# robot_controller.net
KiCad netlist of a schematic drawn in EAGLE
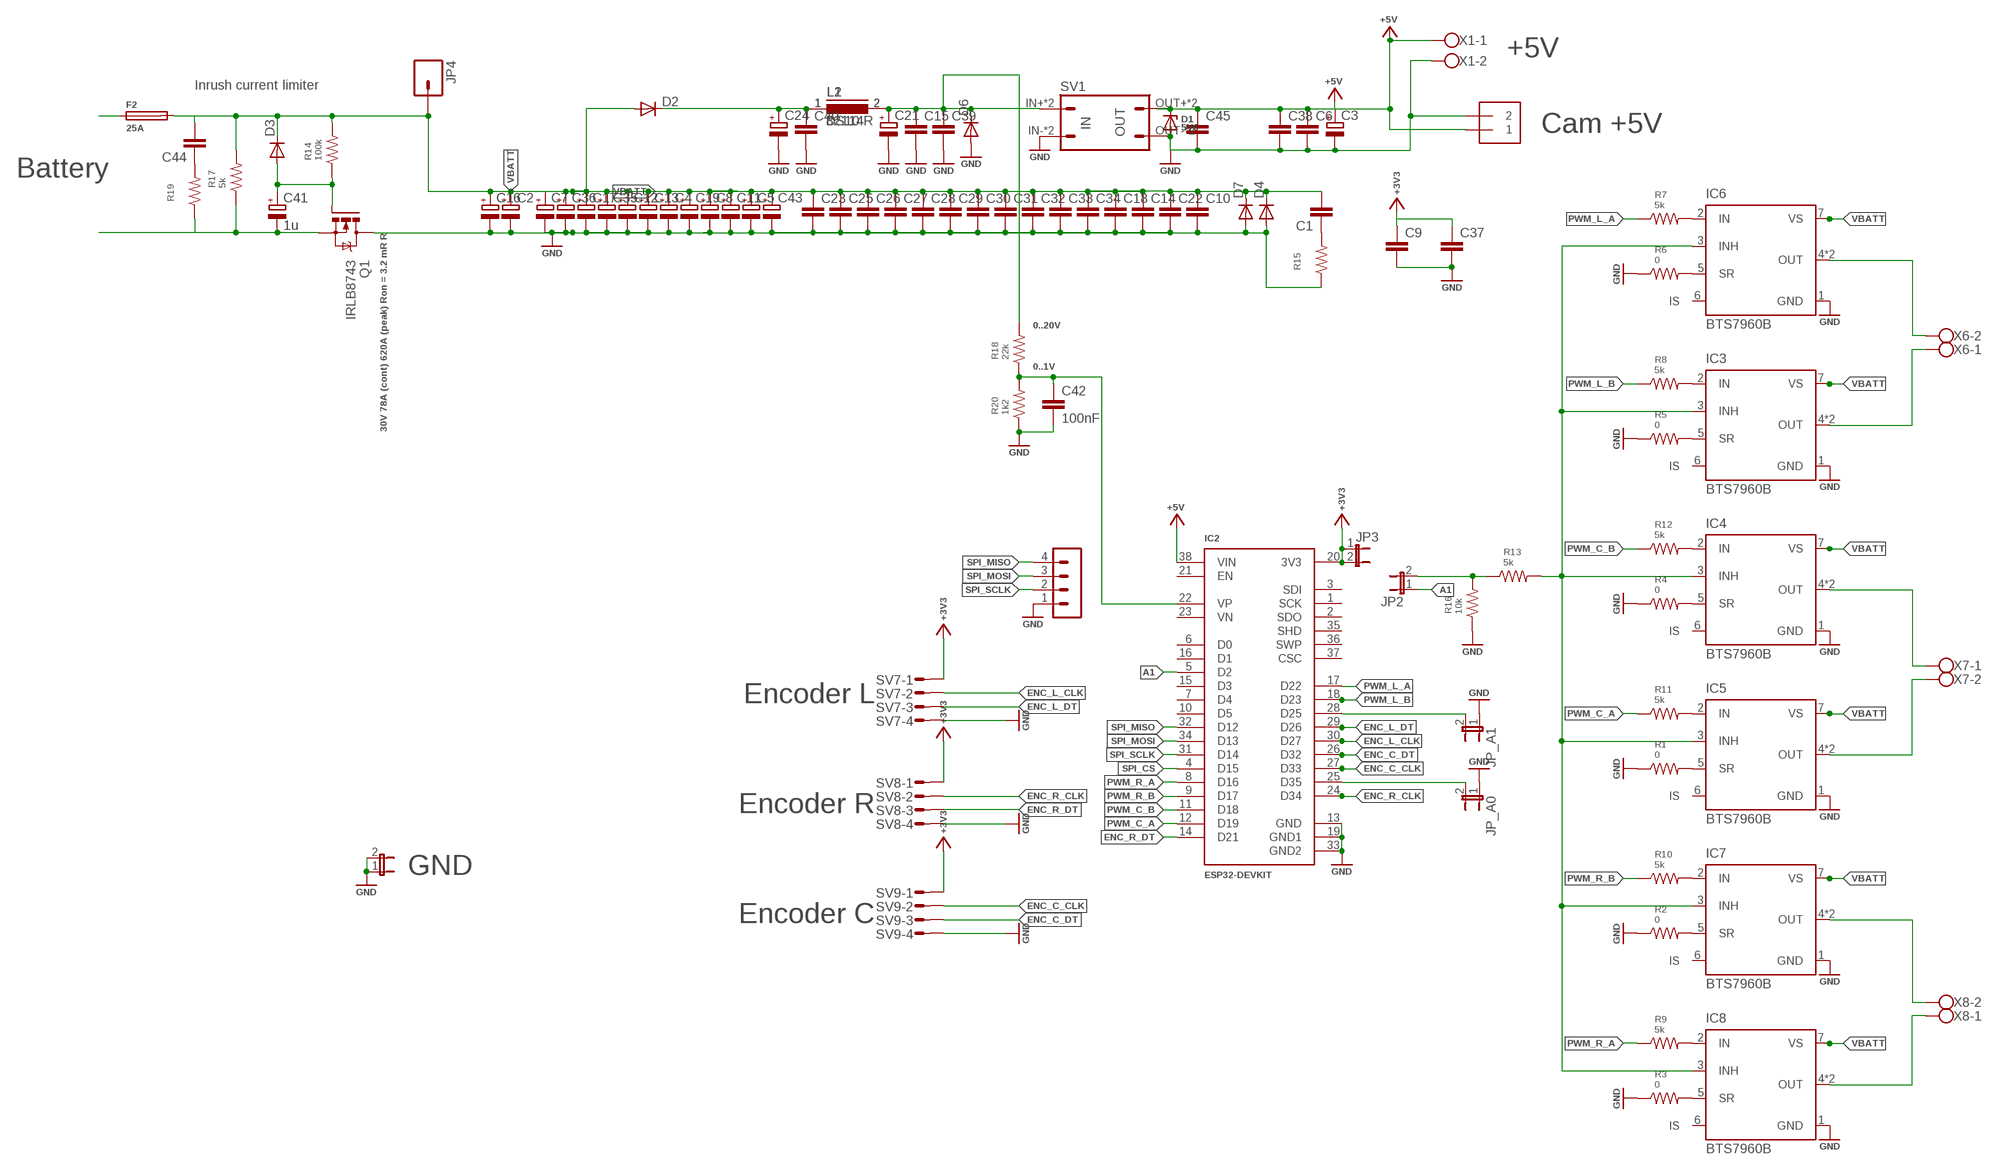
[diagram p0: schematic, sheet 1]

(export (version "E")
  (design (tool "Eeschema 10.0.6"))
  (components
    (comp (ref "C1")
      (value "C-EU025-025X050")
      (footprint "eagle-import:C025-025X050")
      (libsource (lib "eagle-import") (part "C-EU025-025X050"))
    )
    (comp (ref "C2")
      (value "CPOL-EUE5-10.5")
      (footprint "eagle-import:E5-10,5")
      (libsource (lib "eagle-import") (part "CPOL-EUE5-10.5"))
    )
    (comp (ref "C3")
      (value "CPOL-EUE5-10.5")
      (footprint "eagle-import:E5-10,5")
      (libsource (lib "eagle-import") (part "CPOL-EUE5-10.5"))
    )
    (comp (ref "C4")
      (value "CPOL-EUE5-10.5")
      (footprint "eagle-import:E5-10,5")
      (libsource (lib "eagle-import") (part "CPOL-EUE5-10.5"))
    )
    (comp (ref "C5")
      (value "CPOL-EUE5-10.5")
      (footprint "eagle-import:E5-10,5")
      (libsource (lib "eagle-import") (part "CPOL-EUE5-10.5"))
    )
    (comp (ref "C6")
      (value "C-EUC1206")
      (footprint "eagle-import:C1206")
      (libsource (lib "eagle-import") (part "C-EUC1206"))
    )
    (comp (ref "C7")
      (value "CPOL-EUE5-10.5")
      (footprint "eagle-import:E5-10,5")
      (libsource (lib "eagle-import") (part "CPOL-EUE5-10.5"))
    )
    (comp (ref "C8")
      (value "CPOL-EUE5-10.5")
      (footprint "eagle-import:E5-10,5")
      (libsource (lib "eagle-import") (part "CPOL-EUE5-10.5"))
    )
    (comp (ref "C9")
      (value "C-EUC1206")
      (footprint "eagle-import:C1206")
      (libsource (lib "eagle-import") (part "C-EUC1206"))
    )
    (comp (ref "C10")
      (value "C-EUC1206")
      (footprint "eagle-import:C1206")
      (libsource (lib "eagle-import") (part "C-EUC1206"))
    )
    (comp (ref "C11")
      (value "CPOL-EUE5-10.5")
      (footprint "eagle-import:E5-10,5")
      (libsource (lib "eagle-import") (part "CPOL-EUE5-10.5"))
    )
    (comp (ref "C12")
      (value "CPOL-EUE5-10.5")
      (footprint "eagle-import:E5-10,5")
      (libsource (lib "eagle-import") (part "CPOL-EUE5-10.5"))
    )
    (comp (ref "C13")
      (value "CPOL-EUE5-10.5")
      (footprint "eagle-import:E5-10,5")
      (libsource (lib "eagle-import") (part "CPOL-EUE5-10.5"))
    )
    (comp (ref "C14")
      (value "C-EUC1206")
      (footprint "eagle-import:C1206")
      (libsource (lib "eagle-import") (part "C-EUC1206"))
    )
    (comp (ref "C15")
      (value "C-EUC1206")
      (footprint "eagle-import:C1206")
      (libsource (lib "eagle-import") (part "C-EUC1206"))
    )
    (comp (ref "C16")
      (value "CPOL-EUE5-10.5")
      (footprint "eagle-import:E5-10,5")
      (libsource (lib "eagle-import") (part "CPOL-EUE5-10.5"))
    )
    (comp (ref "C17")
      (value "CPOL-EUE5-10.5")
      (footprint "eagle-import:E5-10,5")
      (libsource (lib "eagle-import") (part "CPOL-EUE5-10.5"))
    )
    (comp (ref "C18")
      (value "C-EUC1206")
      (footprint "eagle-import:C1206")
      (libsource (lib "eagle-import") (part "C-EUC1206"))
    )
    (comp (ref "C19")
      (value "CPOL-EUE5-10.5")
      (footprint "eagle-import:E5-10,5")
      (libsource (lib "eagle-import") (part "CPOL-EUE5-10.5"))
    )
    (comp (ref "C21")
      (value "CPOL-EUE5-10.5")
      (footprint "eagle-import:E5-10,5")
      (libsource (lib "eagle-import") (part "CPOL-EUE5-10.5"))
    )
    (comp (ref "C22")
      (value "C-EUC1206")
      (footprint "eagle-import:C1206")
      (libsource (lib "eagle-import") (part "C-EUC1206"))
    )
    (comp (ref "C23")
      (value "C-EUC1206")
      (footprint "eagle-import:C1206")
      (libsource (lib "eagle-import") (part "C-EUC1206"))
    )
    (comp (ref "C24")
      (value "CPOL-EUE5-10.5")
      (footprint "eagle-import:E5-10,5")
      (libsource (lib "eagle-import") (part "CPOL-EUE5-10.5"))
    )
    (comp (ref "C25")
      (value "C-EUC1206")
      (footprint "eagle-import:C1206")
      (libsource (lib "eagle-import") (part "C-EUC1206"))
    )
    (comp (ref "C26")
      (value "C-EUC1206")
      (footprint "eagle-import:C1206")
      (libsource (lib "eagle-import") (part "C-EUC1206"))
    )
    (comp (ref "C27")
      (value "C-EUC1206")
      (footprint "eagle-import:C1206")
      (libsource (lib "eagle-import") (part "C-EUC1206"))
    )
    (comp (ref "C28")
      (value "C-EUC1206")
      (footprint "eagle-import:C1206")
      (libsource (lib "eagle-import") (part "C-EUC1206"))
    )
    (comp (ref "C29")
      (value "C-EUC1206")
      (footprint "eagle-import:C1206")
      (libsource (lib "eagle-import") (part "C-EUC1206"))
    )
    (comp (ref "C30")
      (value "C-EUC1206")
      (footprint "eagle-import:C1206")
      (libsource (lib "eagle-import") (part "C-EUC1206"))
    )
    (comp (ref "C31")
      (value "C-EUC1206")
      (footprint "eagle-import:C1206")
      (libsource (lib "eagle-import") (part "C-EUC1206"))
    )
    (comp (ref "C32")
      (value "C-EUC1206")
      (footprint "eagle-import:C1206")
      (libsource (lib "eagle-import") (part "C-EUC1206"))
    )
    (comp (ref "C33")
      (value "C-EUC1206")
      (footprint "eagle-import:C1206")
      (libsource (lib "eagle-import") (part "C-EUC1206"))
    )
    (comp (ref "C34")
      (value "C-EUC1206")
      (footprint "eagle-import:C1206")
      (libsource (lib "eagle-import") (part "C-EUC1206"))
    )
    (comp (ref "C35")
      (value "CPOL-EUE5-10.5")
      (footprint "eagle-import:E5-10,5")
      (libsource (lib "eagle-import") (part "CPOL-EUE5-10.5"))
    )
    (comp (ref "C36")
      (value "CPOL-EUE5-10.5")
      (footprint "eagle-import:E5-10,5")
      (libsource (lib "eagle-import") (part "CPOL-EUE5-10.5"))
    )
    (comp (ref "C37")
      (value "C-EUC1206")
      (footprint "eagle-import:C1206")
      (libsource (lib "eagle-import") (part "C-EUC1206"))
    )
    (comp (ref "C38")
      (value "C-EUC1206")
      (footprint "eagle-import:C1206")
      (libsource (lib "eagle-import") (part "C-EUC1206"))
    )
    (comp (ref "C39")
      (value "C-EUC1206")
      (footprint "eagle-import:C1206")
      (libsource (lib "eagle-import") (part "C-EUC1206"))
    )
    (comp (ref "C40")
      (value "C-EUC1206")
      (footprint "eagle-import:C1206")
      (libsource (lib "eagle-import") (part "C-EUC1206"))
    )
    (comp (ref "C41")
      (value "1u")
      (footprint "eagle-import:E2,5-6")
      (libsource (lib "eagle-import") (part "CPOL-EUE2.5-6"))
    )
    (comp (ref "C42")
      (value "100nF")
      (footprint "eagle-import:C1206")
      (libsource (lib "eagle-import") (part "C-EUC1206"))
    )
    (comp (ref "C43")
      (value "CPOL-EUE5-10.5")
      (footprint "eagle-import:E5-10,5")
      (libsource (lib "eagle-import") (part "CPOL-EUE5-10.5"))
    )
    (comp (ref "C44")
      (value "C-EU050-030X075")
      (footprint "eagle-import:C050-030X075")
      (libsource (lib "eagle-import") (part "C-EU050-030X075"))
    )
    (comp (ref "C45")
      (value "C-EUC1206")
      (footprint "eagle-import:C1206")
      (libsource (lib "eagle-import") (part "C-EUC1206"))
    )
    (comp (ref "D1")
      (value "5V6")
      (footprint "eagle-import:DO41Z10")
      (libsource (lib "eagle-import") (part "ZENER-DIODEDO41Z10"))
    )
    (comp (ref "D2")
      (value "DIODE-DO15-12")
      (footprint "eagle-import:DO15-12")
      (libsource (lib "eagle-import") (part "DIODE-DO15-12"))
    )
    (comp (ref "D3")
      (value "DIODE-DO-214AC")
      (footprint "eagle-import:DO-214AC")
      (libsource (lib "eagle-import") (part "diode_smd_DIODE-DO-214AC"))
    )
    (comp (ref "D4")
      (value "DIODE-DO41-7.6")
      (footprint "eagle-import:DO41-7.6")
      (libsource (lib "eagle-import") (part "diode_smd_DIODE-DO41-7.6"))
    )
    (comp (ref "D6")
      (value "DIODE-DO15-12")
      (footprint "eagle-import:DO15-12")
      (libsource (lib "eagle-import") (part "DIODE-DO15-12"))
    )
    (comp (ref "D7")
      (value "DIODE-DO41-7.6")
      (footprint "eagle-import:DO41-7.6")
      (libsource (lib "eagle-import") (part "diode_smd_DIODE-DO41-7.6"))
    )
    (comp (ref "F2")
      (value "25A")
      (footprint "eagle-import:SHK20L")
      (libsource (lib "eagle-import") (part "19559"))
    )
    (comp (ref "IC2")
      (value "ESP32-DEVKIT")
      (footprint "eagle-import:DEVKIT-V1-NOHOLES")
      (libsource (lib "eagle-import") (part "ESP32-DEVKIT-V1NOHOLES"))
    )
    (comp (ref "IC3")
      (value "BTS7960B")
      (footprint "eagle-import:P-TO263-7-1")
      (libsource (lib "eagle-import") (part "TLE5205-2G"))
    )
    (comp (ref "IC4")
      (value "BTS7960B")
      (footprint "eagle-import:P-TO263-7-1")
      (libsource (lib "eagle-import") (part "TLE5205-2G"))
    )
    (comp (ref "IC5")
      (value "BTS7960B")
      (footprint "eagle-import:P-TO263-7-1")
      (libsource (lib "eagle-import") (part "TLE5205-2G"))
    )
    (comp (ref "IC6")
      (value "BTS7960B")
      (footprint "eagle-import:P-TO263-7-1")
      (libsource (lib "eagle-import") (part "TLE5205-2G"))
    )
    (comp (ref "IC7")
      (value "BTS7960B")
      (footprint "eagle-import:P-TO263-7-1")
      (libsource (lib "eagle-import") (part "TLE5205-2G"))
    )
    (comp (ref "IC8")
      (value "BTS7960B")
      (footprint "eagle-import:P-TO263-7-1")
      (libsource (lib "eagle-import") (part "TLE5205-2G"))
    )
    (comp (ref "J6")
      (value "1X2-3.5MM")
      (footprint "eagle-import:3.5MMTERM")
      (libsource (lib "eagle-import") (part "1X2-3.5MM"))
    )
    (comp (ref "JP1")
      (value "JP1E")
      (footprint "eagle-import:JP1")
      (libsource (lib "eagle-import") (part "JP1E"))
    )
    (comp (ref "JP2")
      (value "JP1E")
      (footprint "eagle-import:JP1")
      (libsource (lib "eagle-import") (part "JP1E"))
    )
    (comp (ref "JP3")
      (value "JP1E")
      (footprint "eagle-import:JP1")
      (libsource (lib "eagle-import") (part "JP1E"))
    )
    (comp (ref "JP4")
      (value "M01PTH_LONGPAD")
      (footprint "eagle-import:1X01_LONGPAD")
      (libsource (lib "eagle-import") (part "M01PTH_LONGPAD"))
    )
    (comp (ref "JP_A0")
      (value "JP1E")
      (footprint "eagle-import:JP1")
      (libsource (lib "eagle-import") (part "JP1E"))
    )
    (comp (ref "JP_A1")
      (value "JP1E")
      (footprint "eagle-import:JP1")
      (libsource (lib "eagle-import") (part "JP1E"))
    )
    (comp (ref "L1")
      (value "82114R")
      (footprint "eagle-import:82114R")
      (libsource (lib "eagle-import") (part "82114R"))
    )
    (comp (ref "L2")
      (value "DS10")
      (footprint "eagle-import:DS10")
      (libsource (lib "eagle-import") (part "DS10"))
    )
    (comp (ref "Q1")
      (value "IRLB8743")
      (footprint "eagle-import:TO220BV")
      (libsource (lib "eagle-import") (part "IRF540"))
    )
    (comp (ref "R1")
      (value "0")
      (footprint "eagle-import:R1206")
      (libsource (lib "eagle-import") (part "R-US_R1206"))
    )
    (comp (ref "R2")
      (value "0")
      (footprint "eagle-import:R1206")
      (libsource (lib "eagle-import") (part "R-US_R1206"))
    )
    (comp (ref "R3")
      (value "0")
      (footprint "eagle-import:R1206")
      (libsource (lib "eagle-import") (part "R-US_R1206"))
    )
    (comp (ref "R4")
      (value "0")
      (footprint "eagle-import:R1206")
      (libsource (lib "eagle-import") (part "R-US_R1206"))
    )
    (comp (ref "R5")
      (value "0")
      (footprint "eagle-import:R1206")
      (libsource (lib "eagle-import") (part "R-US_R1206"))
    )
    (comp (ref "R6")
      (value "0")
      (footprint "eagle-import:R1206")
      (libsource (lib "eagle-import") (part "R-US_R1206"))
    )
    (comp (ref "R7")
      (value "5k")
      (footprint "eagle-import:R1206")
      (libsource (lib "eagle-import") (part "R-US_R1206"))
    )
    (comp (ref "R8")
      (value "5k")
      (footprint "eagle-import:R1206")
      (libsource (lib "eagle-import") (part "R-US_R1206"))
    )
    (comp (ref "R9")
      (value "5k")
      (footprint "eagle-import:R1206")
      (libsource (lib "eagle-import") (part "R-US_R1206"))
    )
    (comp (ref "R10")
      (value "5k")
      (footprint "eagle-import:R1206")
      (libsource (lib "eagle-import") (part "R-US_R1206"))
    )
    (comp (ref "R11")
      (value "5k")
      (footprint "eagle-import:R1206")
      (libsource (lib "eagle-import") (part "R-US_R1206"))
    )
    (comp (ref "R12")
      (value "5k")
      (footprint "eagle-import:R1206")
      (libsource (lib "eagle-import") (part "R-US_R1206"))
    )
    (comp (ref "R13")
      (value "5k")
      (footprint "eagle-import:R1206")
      (libsource (lib "eagle-import") (part "R-US_R1206"))
    )
    (comp (ref "R14")
      (value "100k")
      (footprint "eagle-import:R1206")
      (libsource (lib "eagle-import") (part "R-US_R1206"))
    )
    (comp (ref "R15")
      (value "R-US_0411/3V")
      (footprint "eagle-import:0411V")
      (libsource (lib "eagle-import") (part "R-US_0411/3V"))
    )
    (comp (ref "R16")
      (value "10k")
      (footprint "eagle-import:R1206")
      (libsource (lib "eagle-import") (part "R-US_R1206"))
    )
    (comp (ref "R17")
      (value "5k")
      (footprint "eagle-import:R1206")
      (libsource (lib "eagle-import") (part "R-US_R1206"))
    )
    (comp (ref "R18")
      (value "22k")
      (footprint "eagle-import:R1206")
      (libsource (lib "eagle-import") (part "R-US_R1206"))
    )
    (comp (ref "R19")
      (value "R-US_0617/5V")
      (footprint "eagle-import:0617V")
      (libsource (lib "eagle-import") (part "R-US_0617/5V"))
    )
    (comp (ref "R20")
      (value "1k2")
      (footprint "eagle-import:R1206")
      (libsource (lib "eagle-import") (part "R-US_R1206"))
    )
    (comp (ref "SV1")
      (value "MA04-1SMALL")
      (footprint "eagle-import:MA04-2")
      (libsource (lib "eagle-import") (part "MA04-1SMALL"))
    )
    (comp (ref "SV6")
      (value "MA04-1")
      (footprint "eagle-import:MA04-1")
      (libsource (lib "eagle-import") (part "MA04-1"))
    )
    (comp (ref "SV7")
      (value "MT6-4")
      (footprint "eagle-import:MT6-4")
      (libsource (lib "eagle-import") (part "MT6-4"))
    )
    (comp (ref "SV8")
      (value "MT6-4")
      (footprint "eagle-import:MT6-4")
      (libsource (lib "eagle-import") (part "MT6-4"))
    )
    (comp (ref "SV9")
      (value "MT6-4")
      (footprint "eagle-import:MT6-4")
      (libsource (lib "eagle-import") (part "MT6-4"))
    )
    (comp (ref "X1")
      (value "W239-302")
      (footprint "eagle-import:W239-302")
      (libsource (lib "eagle-import") (part "W239-302"))
    )
    (comp (ref "X6")
      (value "W239-302")
      (footprint "eagle-import:W239-302")
      (libsource (lib "eagle-import") (part "W239-302"))
    )
    (comp (ref "X7")
      (value "W239-302")
      (footprint "eagle-import:W239-302")
      (libsource (lib "eagle-import") (part "W239-302"))
    )
    (comp (ref "X8")
      (value "W239-302")
      (footprint "eagle-import:W239-302")
      (libsource (lib "eagle-import") (part "W239-302"))
    )
  )
  (nets
    (net (code "1") (name "+3V3") (class "Default")
      (node (ref "C37") (pin "1") (pinfunction "1_1") (pintype "passive"))
      (node (ref "C9") (pin "1") (pinfunction "1_1") (pintype "passive"))
      (node (ref "IC2") (pin "20") (pinfunction "3V3_20") (pintype "output"))
      (node (ref "JP3") (pin "1") (pinfunction "1_1") (pintype "passive"))
      (node (ref "JP3") (pin "2") (pinfunction "2_2") (pintype "passive"))
      (node (ref "SV7") (pin "1") (pinfunction "S_1") (pintype "passive"))
      (node (ref "SV8") (pin "1") (pinfunction "S_1") (pintype "passive"))
      (node (ref "SV9") (pin "1") (pinfunction "S_1") (pintype "passive"))
    )
    (net (code "2") (name "+5V") (class "Default")
      (node (ref "C3") (pin "+") (pinfunction "+_+") (pintype "passive"))
      (node (ref "C38") (pin "1") (pinfunction "1_1") (pintype "passive"))
      (node (ref "C45") (pin "1") (pinfunction "1_1") (pintype "passive"))
      (node (ref "C6") (pin "1") (pinfunction "1_1") (pintype "passive"))
      (node (ref "D1") (pin "C") (pinfunction "C_C") (pintype "passive"))
      (node (ref "IC2") (pin "38") (pinfunction "VIN_38") (pintype "input"))
      (node (ref "J6") (pin "1") (pinfunction "1_1") (pintype "passive"))
      (node (ref "SV1") (pin "OUT+") (pinfunction "OUT+_OUT+") (pintype "passive"))
      (node (ref "SV1") (pin "OUT+1") (pinfunction "OUT+_OUT+1") (pintype "passive"))
      (node (ref "X1") (pin "1") (pinfunction "KL_1") (pintype "passive"))
    )
    (net (code "3") (name "A1") (class "Default")
      (node (ref "IC2") (pin "5") (pinfunction "D2_5") (pintype "bidirectional"))
      (node (ref "JP2") (pin "1") (pinfunction "1_1") (pintype "passive"))
    )
    (net (code "4") (name "ENC_C_CLK") (class "Default")
      (node (ref "IC2") (pin "27") (pinfunction "D33_27") (pintype "bidirectional"))
      (node (ref "SV9") (pin "2") (pinfunction "S_2") (pintype "passive"))
    )
    (net (code "5") (name "ENC_C_DT") (class "Default")
      (node (ref "IC2") (pin "26") (pinfunction "D32_26") (pintype "bidirectional"))
      (node (ref "SV9") (pin "3") (pinfunction "S_3") (pintype "passive"))
    )
    (net (code "6") (name "ENC_L_CLK") (class "Default")
      (node (ref "IC2") (pin "30") (pinfunction "D27_30") (pintype "bidirectional"))
      (node (ref "SV7") (pin "2") (pinfunction "S_2") (pintype "passive"))
    )
    (net (code "7") (name "ENC_L_DT") (class "Default")
      (node (ref "IC2") (pin "29") (pinfunction "D26_29") (pintype "bidirectional"))
      (node (ref "SV7") (pin "3") (pinfunction "S_3") (pintype "passive"))
    )
    (net (code "8") (name "ENC_R_CLK") (class "Default")
      (node (ref "IC2") (pin "24") (pinfunction "D34_24") (pintype "bidirectional"))
      (node (ref "SV8") (pin "2") (pinfunction "S_2") (pintype "passive"))
    )
    (net (code "9") (name "ENC_R_DT") (class "Default")
      (node (ref "IC2") (pin "14") (pinfunction "D21_14") (pintype "bidirectional"))
      (node (ref "SV8") (pin "3") (pinfunction "S_3") (pintype "passive"))
    )
    (net (code "10") (name "GND") (class "Default")
      (node (ref "C10") (pin "2") (pinfunction "2_2") (pintype "passive"))
      (node (ref "C11") (pin "-") (pinfunction "-_-") (pintype "passive"))
      (node (ref "C12") (pin "-") (pinfunction "-_-") (pintype "passive"))
      (node (ref "C13") (pin "-") (pinfunction "-_-") (pintype "passive"))
      (node (ref "C14") (pin "2") (pinfunction "2_2") (pintype "passive"))
      (node (ref "C15") (pin "2") (pinfunction "2_2") (pintype "passive"))
      (node (ref "C16") (pin "-") (pinfunction "-_-") (pintype "passive"))
      (node (ref "C17") (pin "-") (pinfunction "-_-") (pintype "passive"))
      (node (ref "C18") (pin "2") (pinfunction "2_2") (pintype "passive"))
      (node (ref "C19") (pin "-") (pinfunction "-_-") (pintype "passive"))
      (node (ref "C2") (pin "-") (pinfunction "-_-") (pintype "passive"))
      (node (ref "C21") (pin "-") (pinfunction "-_-") (pintype "passive"))
      (node (ref "C22") (pin "2") (pinfunction "2_2") (pintype "passive"))
      (node (ref "C23") (pin "2") (pinfunction "2_2") (pintype "passive"))
      (node (ref "C24") (pin "-") (pinfunction "-_-") (pintype "passive"))
      (node (ref "C25") (pin "2") (pinfunction "2_2") (pintype "passive"))
      (node (ref "C26") (pin "2") (pinfunction "2_2") (pintype "passive"))
      (node (ref "C27") (pin "2") (pinfunction "2_2") (pintype "passive"))
      (node (ref "C28") (pin "2") (pinfunction "2_2") (pintype "passive"))
      (node (ref "C29") (pin "2") (pinfunction "2_2") (pintype "passive"))
      (node (ref "C3") (pin "-") (pinfunction "-_-") (pintype "passive"))
      (node (ref "C30") (pin "2") (pinfunction "2_2") (pintype "passive"))
      (node (ref "C31") (pin "2") (pinfunction "2_2") (pintype "passive"))
      (node (ref "C32") (pin "2") (pinfunction "2_2") (pintype "passive"))
      (node (ref "C33") (pin "2") (pinfunction "2_2") (pintype "passive"))
      (node (ref "C34") (pin "2") (pinfunction "2_2") (pintype "passive"))
      (node (ref "C35") (pin "-") (pinfunction "-_-") (pintype "passive"))
      (node (ref "C36") (pin "-") (pinfunction "-_-") (pintype "passive"))
      (node (ref "C37") (pin "2") (pinfunction "2_2") (pintype "passive"))
      (node (ref "C38") (pin "2") (pinfunction "2_2") (pintype "passive"))
      (node (ref "C39") (pin "2") (pinfunction "2_2") (pintype "passive"))
      (node (ref "C4") (pin "-") (pinfunction "-_-") (pintype "passive"))
      (node (ref "C40") (pin "2") (pinfunction "2_2") (pintype "passive"))
      (node (ref "C42") (pin "2") (pinfunction "2_2") (pintype "passive"))
      (node (ref "C43") (pin "-") (pinfunction "-_-") (pintype "passive"))
      (node (ref "C45") (pin "2") (pinfunction "2_2") (pintype "passive"))
      (node (ref "C5") (pin "-") (pinfunction "-_-") (pintype "passive"))
      (node (ref "C6") (pin "2") (pinfunction "2_2") (pintype "passive"))
      (node (ref "C7") (pin "-") (pinfunction "-_-") (pintype "passive"))
      (node (ref "C8") (pin "-") (pinfunction "-_-") (pintype "passive"))
      (node (ref "C9") (pin "2") (pinfunction "2_2") (pintype "passive"))
      (node (ref "D1") (pin "A") (pinfunction "A_A") (pintype "passive"))
      (node (ref "D4") (pin "A") (pinfunction "A_A") (pintype "passive"))
      (node (ref "D6") (pin "A") (pinfunction "A_A") (pintype "passive"))
      (node (ref "D7") (pin "A") (pinfunction "A_A") (pintype "passive"))
      (node (ref "IC2") (pin "13") (pinfunction "GND_13") (pintype "power_in"))
      (node (ref "IC2") (pin "19") (pinfunction "GND1_19") (pintype "power_in"))
      (node (ref "IC2") (pin "33") (pinfunction "GND2_33") (pintype "power_in"))
      (node (ref "IC3") (pin "1") (pinfunction "GND_1") (pintype "power_in"))
      (node (ref "IC4") (pin "1") (pinfunction "GND_1") (pintype "power_in"))
      (node (ref "IC5") (pin "1") (pinfunction "GND_1") (pintype "power_in"))
      (node (ref "IC6") (pin "1") (pinfunction "GND_1") (pintype "power_in"))
      (node (ref "IC7") (pin "1") (pinfunction "GND_1") (pintype "power_in"))
      (node (ref "IC8") (pin "1") (pinfunction "GND_1") (pintype "power_in"))
      (node (ref "J6") (pin "2") (pinfunction "2_2") (pintype "passive"))
      (node (ref "JP1") (pin "1") (pinfunction "1_1") (pintype "passive"))
      (node (ref "JP1") (pin "2") (pinfunction "2_2") (pintype "passive"))
      (node (ref "JP_A0") (pin "1") (pinfunction "1_1") (pintype "passive"))
      (node (ref "JP_A1") (pin "1") (pinfunction "1_1") (pintype "passive"))
      (node (ref "Q1") (pin "D") (pinfunction "D_D") (pintype "passive"))
      (node (ref "R1") (pin "1") (pinfunction "1_1") (pintype "passive"))
      (node (ref "R15") (pin "1") (pinfunction "1_1") (pintype "passive"))
      (node (ref "R16") (pin "1") (pinfunction "1_1") (pintype "passive"))
      (node (ref "R2") (pin "1") (pinfunction "1_1") (pintype "passive"))
      (node (ref "R20") (pin "1") (pinfunction "1_1") (pintype "passive"))
      (node (ref "R3") (pin "1") (pinfunction "1_1") (pintype "passive"))
      (node (ref "R4") (pin "1") (pinfunction "1_1") (pintype "passive"))
      (node (ref "R5") (pin "1") (pinfunction "1_1") (pintype "passive"))
      (node (ref "R6") (pin "1") (pinfunction "1_1") (pintype "passive"))
      (node (ref "SV1") (pin "IN-") (pinfunction "IN-_IN-") (pintype "passive"))
      (node (ref "SV1") (pin "IN-1") (pinfunction "IN-_IN-1") (pintype "passive"))
      (node (ref "SV1") (pin "OUT-") (pinfunction "OUT-_OUT-") (pintype "passive"))
      (node (ref "SV1") (pin "OUT-1") (pinfunction "OUT-_OUT-1") (pintype "passive"))
      (node (ref "SV6") (pin "1") (pinfunction "1_1") (pintype "passive"))
      (node (ref "SV7") (pin "4") (pinfunction "S_4") (pintype "passive"))
      (node (ref "SV8") (pin "4") (pinfunction "S_4") (pintype "passive"))
      (node (ref "SV9") (pin "4") (pinfunction "S_4") (pintype "passive"))
      (node (ref "X1") (pin "2") (pinfunction "KL_2") (pintype "passive"))
    )
    (net (code "11") (name "Net-(C1-Pad1)") (class "Default")
      (node (ref "C1") (pin "1") (pinfunction "1_1") (pintype "passive"))
      (node (ref "R15") (pin "2") (pinfunction "2_2") (pintype "passive"))
    )
    (net (code "12") (name "Net-(C15-Pad1)") (class "Default")
      (node (ref "C15") (pin "1") (pinfunction "1_1") (pintype "passive"))
      (node (ref "C21") (pin "+") (pinfunction "+_+") (pintype "passive"))
      (node (ref "C39") (pin "1") (pinfunction "1_1") (pintype "passive"))
      (node (ref "D6") (pin "C") (pinfunction "C_C") (pintype "passive"))
      (node (ref "L1") (pin "2") (pinfunction "2_2") (pintype "passive"))
      (node (ref "L2") (pin "2") (pinfunction "2_2") (pintype "passive"))
      (node (ref "R18") (pin "2") (pinfunction "2_2") (pintype "passive"))
      (node (ref "SV1") (pin "IN+") (pinfunction "IN+_IN+") (pintype "passive"))
      (node (ref "SV1") (pin "IN+1") (pinfunction "IN+_IN+1") (pintype "passive"))
    )
    (net (code "13") (name "Net-(C24-Pad+)") (class "Default")
      (node (ref "C24") (pin "+") (pinfunction "+_+") (pintype "passive"))
      (node (ref "C40") (pin "1") (pinfunction "1_1") (pintype "passive"))
      (node (ref "D2") (pin "C") (pinfunction "C_C") (pintype "passive"))
      (node (ref "L1") (pin "1") (pinfunction "1_1") (pintype "passive"))
      (node (ref "L2") (pin "1") (pinfunction "1_1") (pintype "passive"))
    )
    (net (code "14") (name "Net-(C41-Pad+)") (class "Default")
      (node (ref "C41") (pin "+") (pinfunction "+_+") (pintype "passive"))
      (node (ref "D3") (pin "A") (pinfunction "A_A") (pintype "passive"))
      (node (ref "Q1") (pin "G") (pinfunction "G_G") (pintype "passive"))
      (node (ref "R14") (pin "1") (pinfunction "1_1") (pintype "passive"))
    )
    (net (code "15") (name "Net-(C41-Pad-)") (class "Default")
      (node (ref "C41") (pin "-") (pinfunction "-_-") (pintype "passive"))
      (node (ref "Q1") (pin "S") (pinfunction "S_S") (pintype "passive"))
      (node (ref "R17") (pin "1") (pinfunction "1_1") (pintype "passive"))
      (node (ref "R19") (pin "1") (pinfunction "1_1") (pintype "passive"))
    )
    (net (code "16") (name "Net-(C44-Pad1)") (class "Default")
      (node (ref "C44") (pin "1") (pinfunction "1_1") (pintype "passive"))
      (node (ref "R19") (pin "2") (pinfunction "2_2") (pintype "passive"))
    )
    (net (code "17") (name "Net-(F2-1-Pad1A)") (class "Default")
      (node (ref "F2") (pin "1A") (pinfunction "1_1A") (pintype "passive"))
      (node (ref "F2") (pin "1B") (pinfunction "1_1B") (pintype "passive"))
    )
    (net (code "18") (name "Net-(IC2-D25)") (class "Default")
      (node (ref "IC2") (pin "28") (pinfunction "D25_28") (pintype "bidirectional"))
      (node (ref "JP_A1") (pin "2") (pinfunction "2_2") (pintype "passive"))
    )
    (net (code "19") (name "Net-(IC2-D35)") (class "Default")
      (node (ref "IC2") (pin "25") (pinfunction "D35_25") (pintype "bidirectional"))
      (node (ref "JP_A0") (pin "2") (pinfunction "2_2") (pintype "passive"))
    )
    (net (code "20") (name "Net-(IC2-VP)") (class "Default")
      (node (ref "C42") (pin "1") (pinfunction "1_1") (pintype "passive"))
      (node (ref "IC2") (pin "22") (pinfunction "VP_22") (pintype "bidirectional"))
      (node (ref "R18") (pin "1") (pinfunction "1_1") (pintype "passive"))
      (node (ref "R20") (pin "2") (pinfunction "2_2") (pintype "passive"))
    )
    (net (code "21") (name "Net-(IC3-IN)") (class "Default")
      (node (ref "IC3") (pin "2") (pinfunction "IN_2") (pintype "open_collector"))
      (node (ref "R8") (pin "2") (pinfunction "2_2") (pintype "passive"))
    )
    (net (code "22") (name "Net-(IC3-INH)") (class "Default")
      (node (ref "IC3") (pin "3") (pinfunction "INH_3") (pintype "input"))
      (node (ref "IC4") (pin "3") (pinfunction "INH_3") (pintype "input"))
      (node (ref "IC5") (pin "3") (pinfunction "INH_3") (pintype "input"))
      (node (ref "IC6") (pin "3") (pinfunction "INH_3") (pintype "input"))
      (node (ref "IC7") (pin "3") (pinfunction "INH_3") (pintype "input"))
      (node (ref "IC8") (pin "3") (pinfunction "INH_3") (pintype "input"))
      (node (ref "R13") (pin "2") (pinfunction "2_2") (pintype "passive"))
    )
    (net (code "23") (name "Net-(IC3-SR)") (class "Default")
      (node (ref "IC3") (pin "5") (pinfunction "SR_5") (pintype "input"))
      (node (ref "R5") (pin "2") (pinfunction "2_2") (pintype "passive"))
    )
    (net (code "24") (name "Net-(IC4-IN)") (class "Default")
      (node (ref "IC4") (pin "2") (pinfunction "IN_2") (pintype "open_collector"))
      (node (ref "R12") (pin "2") (pinfunction "2_2") (pintype "passive"))
    )
    (net (code "25") (name "Net-(IC4-SR)") (class "Default")
      (node (ref "IC4") (pin "5") (pinfunction "SR_5") (pintype "input"))
      (node (ref "R4") (pin "2") (pinfunction "2_2") (pintype "passive"))
    )
    (net (code "26") (name "Net-(IC5-IN)") (class "Default")
      (node (ref "IC5") (pin "2") (pinfunction "IN_2") (pintype "open_collector"))
      (node (ref "R11") (pin "2") (pinfunction "2_2") (pintype "passive"))
    )
    (net (code "27") (name "Net-(IC5-SR)") (class "Default")
      (node (ref "IC5") (pin "5") (pinfunction "SR_5") (pintype "input"))
      (node (ref "R1") (pin "2") (pinfunction "2_2") (pintype "passive"))
    )
    (net (code "28") (name "Net-(IC6-IN)") (class "Default")
      (node (ref "IC6") (pin "2") (pinfunction "IN_2") (pintype "open_collector"))
      (node (ref "R7") (pin "2") (pinfunction "2_2") (pintype "passive"))
    )
    (net (code "29") (name "Net-(IC6-SR)") (class "Default")
      (node (ref "IC6") (pin "5") (pinfunction "SR_5") (pintype "input"))
      (node (ref "R6") (pin "2") (pinfunction "2_2") (pintype "passive"))
    )
    (net (code "30") (name "Net-(IC7-IN)") (class "Default")
      (node (ref "IC7") (pin "2") (pinfunction "IN_2") (pintype "open_collector"))
      (node (ref "R10") (pin "2") (pinfunction "2_2") (pintype "passive"))
    )
    (net (code "31") (name "Net-(IC7-SR)") (class "Default")
      (node (ref "IC7") (pin "5") (pinfunction "SR_5") (pintype "input"))
      (node (ref "R2") (pin "2") (pinfunction "2_2") (pintype "passive"))
    )
    (net (code "32") (name "Net-(IC8-IN)") (class "Default")
      (node (ref "IC8") (pin "2") (pinfunction "IN_2") (pintype "open_collector"))
      (node (ref "R9") (pin "2") (pinfunction "2_2") (pintype "passive"))
    )
    (net (code "33") (name "Net-(IC8-SR)") (class "Default")
      (node (ref "IC8") (pin "5") (pinfunction "SR_5") (pintype "input"))
      (node (ref "R3") (pin "2") (pinfunction "2_2") (pintype "passive"))
    )
    (net (code "34") (name "Net-(JP2-Pad2)") (class "Default")
      (node (ref "JP2") (pin "2") (pinfunction "2_2") (pintype "passive"))
      (node (ref "R13") (pin "1") (pinfunction "1_1") (pintype "passive"))
      (node (ref "R16") (pin "2") (pinfunction "2_2") (pintype "passive"))
    )
    (net (code "35") (name "Net-(X6A-KL)") (class "Default")
      (node (ref "IC3") (pin "4") (pinfunction "OUT_4") (pintype "output"))
      (node (ref "IC3") (pin "8") (pinfunction "OUT_8") (pintype "output"))
      (node (ref "X6") (pin "1") (pinfunction "KL_1") (pintype "passive"))
    )
    (net (code "36") (name "Net-(X6B-KL)") (class "Default")
      (node (ref "IC6") (pin "4") (pinfunction "OUT_4") (pintype "output"))
      (node (ref "IC6") (pin "8") (pinfunction "OUT_8") (pintype "output"))
      (node (ref "X6") (pin "2") (pinfunction "KL_2") (pintype "passive"))
    )
    (net (code "37") (name "Net-(X7A-KL)") (class "Default")
      (node (ref "IC4") (pin "4") (pinfunction "OUT_4") (pintype "output"))
      (node (ref "IC4") (pin "8") (pinfunction "OUT_8") (pintype "output"))
      (node (ref "X7") (pin "1") (pinfunction "KL_1") (pintype "passive"))
    )
    (net (code "38") (name "Net-(X7B-KL)") (class "Default")
      (node (ref "IC5") (pin "4") (pinfunction "OUT_4") (pintype "output"))
      (node (ref "IC5") (pin "8") (pinfunction "OUT_8") (pintype "output"))
      (node (ref "X7") (pin "2") (pinfunction "KL_2") (pintype "passive"))
    )
    (net (code "39") (name "Net-(X8A-KL)") (class "Default")
      (node (ref "IC8") (pin "4") (pinfunction "OUT_4") (pintype "output"))
      (node (ref "IC8") (pin "8") (pinfunction "OUT_8") (pintype "output"))
      (node (ref "X8") (pin "1") (pinfunction "KL_1") (pintype "passive"))
    )
    (net (code "40") (name "Net-(X8B-KL)") (class "Default")
      (node (ref "IC7") (pin "4") (pinfunction "OUT_4") (pintype "output"))
      (node (ref "IC7") (pin "8") (pinfunction "OUT_8") (pintype "output"))
      (node (ref "X8") (pin "2") (pinfunction "KL_2") (pintype "passive"))
    )
    (net (code "41") (name "PWM_C_A") (class "Default")
      (node (ref "IC2") (pin "12") (pinfunction "D19_12") (pintype "bidirectional"))
      (node (ref "R11") (pin "1") (pinfunction "1_1") (pintype "passive"))
    )
    (net (code "42") (name "PWM_C_B") (class "Default")
      (node (ref "IC2") (pin "11") (pinfunction "D18_11") (pintype "bidirectional"))
      (node (ref "R12") (pin "1") (pinfunction "1_1") (pintype "passive"))
    )
    (net (code "43") (name "PWM_L_A") (class "Default")
      (node (ref "IC2") (pin "17") (pinfunction "D22_17") (pintype "bidirectional"))
      (node (ref "R7") (pin "1") (pinfunction "1_1") (pintype "passive"))
    )
    (net (code "44") (name "PWM_L_B") (class "Default")
      (node (ref "IC2") (pin "18") (pinfunction "D23_18") (pintype "bidirectional"))
      (node (ref "R8") (pin "1") (pinfunction "1_1") (pintype "passive"))
    )
    (net (code "45") (name "PWM_R_A") (class "Default")
      (node (ref "IC2") (pin "8") (pinfunction "D16_8") (pintype "bidirectional"))
      (node (ref "R9") (pin "1") (pinfunction "1_1") (pintype "passive"))
    )
    (net (code "46") (name "PWM_R_B") (class "Default")
      (node (ref "IC2") (pin "9") (pinfunction "D17_9") (pintype "bidirectional"))
      (node (ref "R10") (pin "1") (pinfunction "1_1") (pintype "passive"))
    )
    (net (code "47") (name "SPI_CS") (class "Default")
      (node (ref "IC2") (pin "4") (pinfunction "D15_4") (pintype "bidirectional"))
    )
    (net (code "48") (name "SPI_MISO") (class "Default")
      (node (ref "IC2") (pin "32") (pinfunction "D12_32") (pintype "bidirectional"))
      (node (ref "SV6") (pin "4") (pinfunction "4_4") (pintype "passive"))
    )
    (net (code "49") (name "SPI_MOSI") (class "Default")
      (node (ref "IC2") (pin "34") (pinfunction "D13_34") (pintype "bidirectional"))
      (node (ref "SV6") (pin "3") (pinfunction "3_3") (pintype "passive"))
    )
    (net (code "50") (name "SPI_SCLK") (class "Default")
      (node (ref "IC2") (pin "31") (pinfunction "D14_31") (pintype "bidirectional"))
      (node (ref "SV6") (pin "2") (pinfunction "2_2") (pintype "passive"))
    )
    (net (code "51") (name "VBATT") (class "Default")
      (node (ref "C1") (pin "2") (pinfunction "2_2") (pintype "passive"))
      (node (ref "C10") (pin "1") (pinfunction "1_1") (pintype "passive"))
      (node (ref "C11") (pin "+") (pinfunction "+_+") (pintype "passive"))
      (node (ref "C12") (pin "+") (pinfunction "+_+") (pintype "passive"))
      (node (ref "C13") (pin "+") (pinfunction "+_+") (pintype "passive"))
      (node (ref "C14") (pin "1") (pinfunction "1_1") (pintype "passive"))
      (node (ref "C16") (pin "+") (pinfunction "+_+") (pintype "passive"))
      (node (ref "C17") (pin "+") (pinfunction "+_+") (pintype "passive"))
      (node (ref "C18") (pin "1") (pinfunction "1_1") (pintype "passive"))
      (node (ref "C19") (pin "+") (pinfunction "+_+") (pintype "passive"))
      (node (ref "C2") (pin "+") (pinfunction "+_+") (pintype "passive"))
      (node (ref "C22") (pin "1") (pinfunction "1_1") (pintype "passive"))
      (node (ref "C23") (pin "1") (pinfunction "1_1") (pintype "passive"))
      (node (ref "C25") (pin "1") (pinfunction "1_1") (pintype "passive"))
      (node (ref "C26") (pin "1") (pinfunction "1_1") (pintype "passive"))
      (node (ref "C27") (pin "1") (pinfunction "1_1") (pintype "passive"))
      (node (ref "C28") (pin "1") (pinfunction "1_1") (pintype "passive"))
      (node (ref "C29") (pin "1") (pinfunction "1_1") (pintype "passive"))
      (node (ref "C30") (pin "1") (pinfunction "1_1") (pintype "passive"))
      (node (ref "C31") (pin "1") (pinfunction "1_1") (pintype "passive"))
      (node (ref "C32") (pin "1") (pinfunction "1_1") (pintype "passive"))
      (node (ref "C33") (pin "1") (pinfunction "1_1") (pintype "passive"))
      (node (ref "C34") (pin "1") (pinfunction "1_1") (pintype "passive"))
      (node (ref "C35") (pin "+") (pinfunction "+_+") (pintype "passive"))
      (node (ref "C36") (pin "+") (pinfunction "+_+") (pintype "passive"))
      (node (ref "C4") (pin "+") (pinfunction "+_+") (pintype "passive"))
      (node (ref "C43") (pin "+") (pinfunction "+_+") (pintype "passive"))
      (node (ref "C44") (pin "2") (pinfunction "2_2") (pintype "passive"))
      (node (ref "C5") (pin "+") (pinfunction "+_+") (pintype "passive"))
      (node (ref "C7") (pin "+") (pinfunction "+_+") (pintype "passive"))
      (node (ref "C8") (pin "+") (pinfunction "+_+") (pintype "passive"))
      (node (ref "D2") (pin "A") (pinfunction "A_A") (pintype "passive"))
      (node (ref "D3") (pin "C") (pinfunction "C_C") (pintype "passive"))
      (node (ref "D4") (pin "C") (pinfunction "C_C") (pintype "passive"))
      (node (ref "D7") (pin "C") (pinfunction "C_C") (pintype "passive"))
      (node (ref "F2") (pin "2A") (pinfunction "2_2A") (pintype "passive"))
      (node (ref "F2") (pin "2B") (pinfunction "2_2B") (pintype "passive"))
      (node (ref "IC3") (pin "7") (pinfunction "VS_7") (pintype "input"))
      (node (ref "IC4") (pin "7") (pinfunction "VS_7") (pintype "input"))
      (node (ref "IC5") (pin "7") (pinfunction "VS_7") (pintype "input"))
      (node (ref "IC6") (pin "7") (pinfunction "VS_7") (pintype "input"))
      (node (ref "IC7") (pin "7") (pinfunction "VS_7") (pintype "input"))
      (node (ref "IC8") (pin "7") (pinfunction "VS_7") (pintype "input"))
      (node (ref "JP4") (pin "1") (pinfunction "1_1") (pintype "passive"))
      (node (ref "R14") (pin "2") (pinfunction "2_2") (pintype "passive"))
      (node (ref "R17") (pin "2") (pinfunction "2_2") (pintype "passive"))
    )
    (net (code "52") (name "unconnected-(IC2-CSC-Pad37)") (class "Default")
      (node (ref "IC2") (pin "37") (pinfunction "CSC_37") (pintype "output"))
    )
    (net (code "53") (name "unconnected-(IC2-D0-Pad6)") (class "Default")
      (node (ref "IC2") (pin "6") (pinfunction "D0_6") (pintype "bidirectional"))
    )
    (net (code "54") (name "unconnected-(IC2-D1-Pad16)") (class "Default")
      (node (ref "IC2") (pin "16") (pinfunction "D1_16") (pintype "bidirectional"))
    )
    (net (code "55") (name "unconnected-(IC2-D3-Pad15)") (class "Default")
      (node (ref "IC2") (pin "15") (pinfunction "D3_15") (pintype "bidirectional"))
    )
    (net (code "56") (name "unconnected-(IC2-D4-Pad7)") (class "Default")
      (node (ref "IC2") (pin "7") (pinfunction "D4_7") (pintype "bidirectional"))
    )
    (net (code "57") (name "unconnected-(IC2-D5-Pad10)") (class "Default")
      (node (ref "IC2") (pin "10") (pinfunction "D5_10") (pintype "bidirectional"))
    )
    (net (code "58") (name "unconnected-(IC2-EN-Pad21)") (class "Default")
      (node (ref "IC2") (pin "21") (pinfunction "EN_21") (pintype "input"))
    )
    (net (code "59") (name "unconnected-(IC2-SCK-Pad1)") (class "Default")
      (node (ref "IC2") (pin "1") (pinfunction "SCK_1") (pintype "output"))
    )
    (net (code "60") (name "unconnected-(IC2-SDI-Pad3)") (class "Default")
      (node (ref "IC2") (pin "3") (pinfunction "SDI_3") (pintype "input"))
    )
    (net (code "61") (name "unconnected-(IC2-SDO-Pad2)") (class "Default")
      (node (ref "IC2") (pin "2") (pinfunction "SDO_2") (pintype "input"))
    )
    (net (code "62") (name "unconnected-(IC2-SHD-Pad35)") (class "Default")
      (node (ref "IC2") (pin "35") (pinfunction "SHD_35") (pintype "input"))
    )
    (net (code "63") (name "unconnected-(IC2-SWP-Pad36)") (class "Default")
      (node (ref "IC2") (pin "36") (pinfunction "SWP_36") (pintype "output"))
    )
    (net (code "64") (name "unconnected-(IC2-VN-Pad23)") (class "Default")
      (node (ref "IC2") (pin "23") (pinfunction "VN_23") (pintype "bidirectional"))
    )
    (net (code "65") (name "unconnected-(IC3-IS-Pad6)") (class "Default")
      (node (ref "IC3") (pin "6") (pinfunction "IS_6") (pintype "output"))
    )
    (net (code "66") (name "unconnected-(IC4-IS-Pad6)") (class "Default")
      (node (ref "IC4") (pin "6") (pinfunction "IS_6") (pintype "output"))
    )
    (net (code "67") (name "unconnected-(IC5-IS-Pad6)") (class "Default")
      (node (ref "IC5") (pin "6") (pinfunction "IS_6") (pintype "output"))
    )
    (net (code "68") (name "unconnected-(IC6-IS-Pad6)") (class "Default")
      (node (ref "IC6") (pin "6") (pinfunction "IS_6") (pintype "output"))
    )
    (net (code "69") (name "unconnected-(IC7-IS-Pad6)") (class "Default")
      (node (ref "IC7") (pin "6") (pinfunction "IS_6") (pintype "output"))
    )
    (net (code "70") (name "unconnected-(IC8-IS-Pad6)") (class "Default")
      (node (ref "IC8") (pin "6") (pinfunction "IS_6") (pintype "output"))
    )
  )
)
